# LAUNCHXL-F28379D_4.net
KiCad netlist of a schematic drawn in Altium Designer
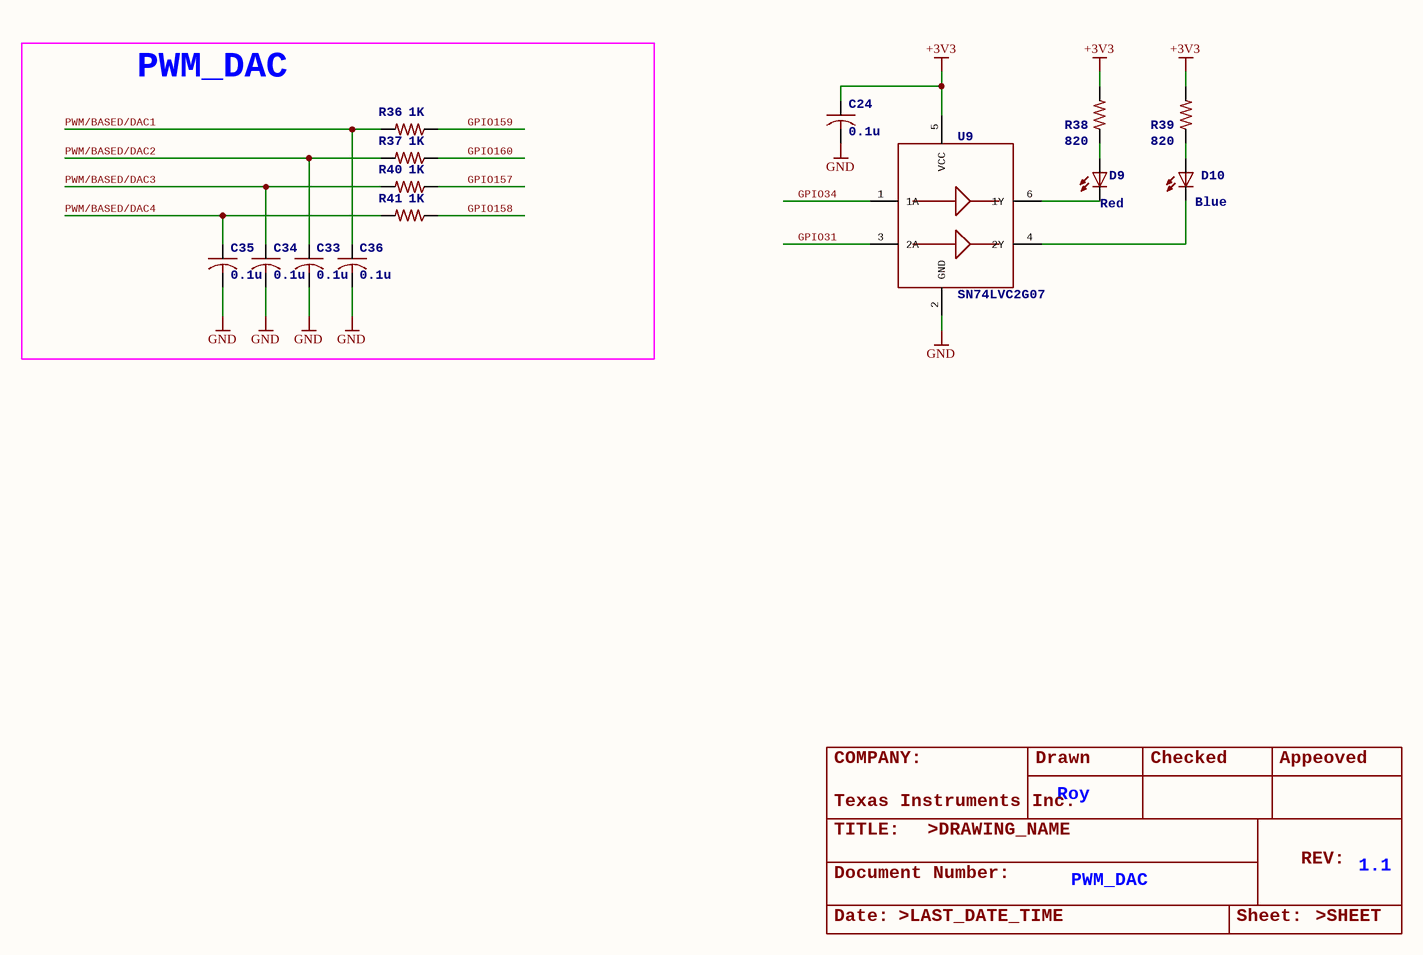
[diagram p0: LAUNCHXL-F28379D_4.SchDoc]

(export (version "E")
  (design (tool "Eeschema 10.0.6"))
  (components
    (comp (ref "C24")
      (value "0.1u")
      (footprint "C0402")
      (description "<B>CAPACITOR</B>, American symbol")
      (libsource (lib "rcl") (part "C-USC0402"))
    )
    (comp (ref "C33")
      (value "0.1u")
      (footprint "C0402")
      (description "<B>CAPACITOR</B>, American symbol")
      (libsource (lib "rcl") (part "C-USC0402"))
    )
    (comp (ref "C34")
      (value "0.1u")
      (footprint "C0402")
      (description "<B>CAPACITOR</B>, American symbol")
      (libsource (lib "rcl") (part "C-USC0402"))
    )
    (comp (ref "C35")
      (value "0.1u")
      (footprint "C0402")
      (description "<B>CAPACITOR</B>, American symbol")
      (libsource (lib "rcl") (part "C-USC0402"))
    )
    (comp (ref "C36")
      (value "0.1u")
      (footprint "C0402")
      (description "<B>CAPACITOR</B>, American symbol")
      (libsource (lib "rcl") (part "C-USC0402"))
    )
    (comp (ref "D9")
      (value "Red")
      (footprint "CHIP-LED0603")
      (libsource (lib "led") (part "LEDCHIP-LED0603"))
    )
    (comp (ref "D10")
      (value "Blue")
      (footprint "CHIP-LED0603")
      (libsource (lib "led") (part "LEDCHIP-LED0603"))
    )
    (comp (ref "R36")
      (value "1K")
      (footprint "R0402")
      (description "<B>RESISTOR</B>, American symbol")
      (libsource (lib "rcl") (part "R-US_R0402"))
    )
    (comp (ref "R37")
      (value "1K")
      (footprint "R0402")
      (description "<B>RESISTOR</B>, American symbol")
      (libsource (lib "rcl") (part "R-US_R0402"))
    )
    (comp (ref "R38")
      (value "820")
      (footprint "R0402")
      (description "<B>RESISTOR</B>, American symbol")
      (libsource (lib "rcl") (part "R-US_R0402"))
    )
    (comp (ref "R39")
      (value "820")
      (footprint "R0402")
      (description "<B>RESISTOR</B>, American symbol")
      (libsource (lib "rcl") (part "R-US_R0402"))
    )
    (comp (ref "R40")
      (value "1K")
      (footprint "R0402")
      (description "<B>RESISTOR</B>, American symbol")
      (libsource (lib "rcl") (part "R-US_R0402"))
    )
    (comp (ref "R41")
      (value "1K")
      (footprint "R0402")
      (description "<B>RESISTOR</B>, American symbol")
      (libsource (lib "rcl") (part "R-US_R0402"))
    )
    (comp (ref "U9")
      (value "SN74LVC2G07")
      (footprint "SOT23-6-DBV")
      (libsource (lib "texas") (part "SN74LVC2G07"))
    )
  )
  (nets
    (net (code "1") (name "+3V3") (class "Default")
      (node (ref "C24") (pin "1") (pinfunction "1_1") (pintype "passive"))
      (node (ref "R38") (pin "2") (pinfunction "2_2") (pintype "passive"))
      (node (ref "R39") (pin "2") (pinfunction "2_2") (pintype "passive"))
      (node (ref "U9") (pin "5") (pinfunction "VCC_5") (pintype "passive"))
    )
    (net (code "2") (name "/GPIO31") (class "Default")
      (node (ref "U9") (pin "3") (pinfunction "2A_3") (pintype "passive"))
    )
    (net (code "3") (name "/GPIO34") (class "Default")
      (node (ref "U9") (pin "1") (pinfunction "1A_1") (pintype "passive"))
    )
    (net (code "4") (name "/GPIO157") (class "Default")
      (node (ref "R40") (pin "1") (pinfunction "1_1") (pintype "passive"))
    )
    (net (code "5") (name "/GPIO158") (class "Default")
      (node (ref "R41") (pin "1") (pinfunction "1_1") (pintype "passive"))
    )
    (net (code "6") (name "/GPIO159") (class "Default")
      (node (ref "R36") (pin "1") (pinfunction "1_1") (pintype "passive"))
    )
    (net (code "7") (name "/GPIO160") (class "Default")
      (node (ref "R37") (pin "1") (pinfunction "1_1") (pintype "passive"))
    )
    (net (code "8") (name "/PWM{slash}BASED{slash}DAC1") (class "Default")
      (node (ref "C36") (pin "1") (pinfunction "1_1") (pintype "passive"))
      (node (ref "R36") (pin "2") (pinfunction "2_2") (pintype "passive"))
    )
    (net (code "9") (name "/PWM{slash}BASED{slash}DAC2") (class "Default")
      (node (ref "C33") (pin "1") (pinfunction "1_1") (pintype "passive"))
      (node (ref "R37") (pin "2") (pinfunction "2_2") (pintype "passive"))
    )
    (net (code "10") (name "/PWM{slash}BASED{slash}DAC3") (class "Default")
      (node (ref "C34") (pin "1") (pinfunction "1_1") (pintype "passive"))
      (node (ref "R40") (pin "2") (pinfunction "2_2") (pintype "passive"))
    )
    (net (code "11") (name "/PWM{slash}BASED{slash}DAC4") (class "Default")
      (node (ref "C35") (pin "1") (pinfunction "1_1") (pintype "passive"))
      (node (ref "R41") (pin "2") (pinfunction "2_2") (pintype "passive"))
    )
    (net (code "12") (name "GND") (class "Default")
      (node (ref "C24") (pin "2") (pinfunction "2_2") (pintype "passive"))
      (node (ref "C33") (pin "2") (pinfunction "2_2") (pintype "passive"))
      (node (ref "C34") (pin "2") (pinfunction "2_2") (pintype "passive"))
      (node (ref "C35") (pin "2") (pinfunction "2_2") (pintype "passive"))
      (node (ref "C36") (pin "2") (pinfunction "2_2") (pintype "passive"))
      (node (ref "U9") (pin "2") (pinfunction "GND_2") (pintype "passive"))
    )
    (net (code "13") (name "Net-(D9-PadA)") (class "Default")
      (node (ref "D9") (pin "A") (pinfunction "A_A") (pintype "passive"))
      (node (ref "R38") (pin "1") (pinfunction "1_1") (pintype "passive"))
    )
    (net (code "14") (name "Net-(D10-PadA)") (class "Default")
      (node (ref "D10") (pin "A") (pinfunction "A_A") (pintype "passive"))
      (node (ref "R39") (pin "1") (pinfunction "1_1") (pintype "passive"))
    )
    (net (code "15") (name "Net-(U9-1Y)") (class "Default")
      (node (ref "D9") (pin "C") (pinfunction "C_C") (pintype "passive"))
      (node (ref "U9") (pin "6") (pinfunction "1Y_6") (pintype "passive"))
    )
    (net (code "16") (name "Net-(U9-2Y)") (class "Default")
      (node (ref "D10") (pin "C") (pinfunction "C_C") (pintype "passive"))
      (node (ref "U9") (pin "4") (pinfunction "2Y_4") (pintype "passive"))
    )
  )
)
